# tester.net
KiCad netlist of a schematic drawn in EAGLE
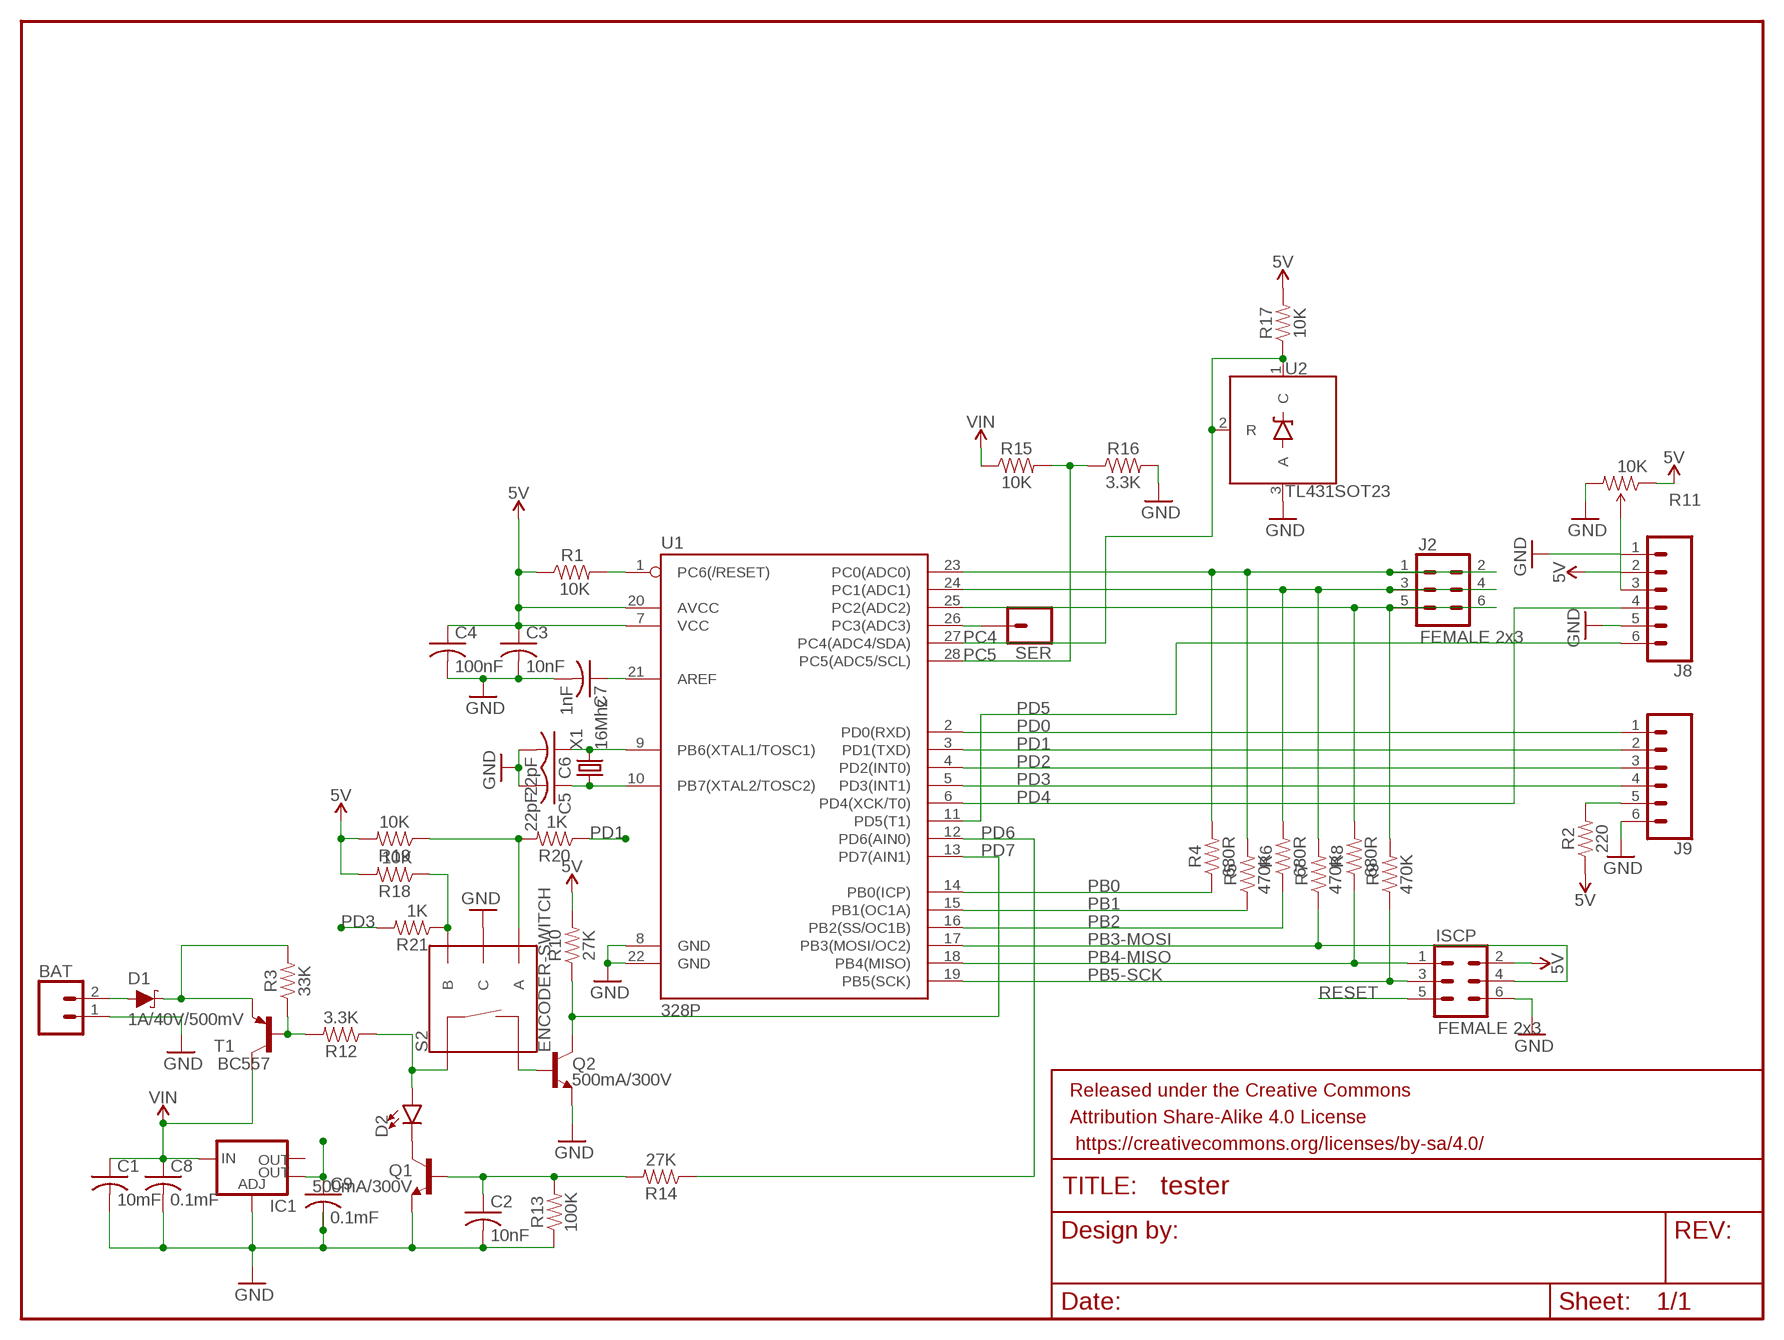
[diagram p0: schematic, sheet 1]

(export (version "E")
  (design (tool "Eeschema 10.0.6"))
  (components
    (comp (ref "BAT")
      (value "CONN_02")
      (footprint "eagle-import:1X02")
      (libsource (lib "eagle-import") (part "CONN_02"))
    )
    (comp (ref "C1")
      (value "10mF")
      (footprint "eagle-import:C0805")
      (libsource (lib "eagle-import") (part "C-USC0805"))
    )
    (comp (ref "C2")
      (value "10nF")
      (footprint "eagle-import:C0805")
      (libsource (lib "eagle-import") (part "C-USC0805"))
    )
    (comp (ref "C3")
      (value "10nF")
      (footprint "eagle-import:C0805")
      (libsource (lib "eagle-import") (part "C-USC0805"))
    )
    (comp (ref "C4")
      (value "100nF")
      (footprint "eagle-import:C0805")
      (libsource (lib "eagle-import") (part "C-USC0805"))
    )
    (comp (ref "C5")
      (value "22pF")
      (footprint "eagle-import:C0805")
      (libsource (lib "eagle-import") (part "C-USC0805"))
    )
    (comp (ref "C6")
      (value "22pF")
      (footprint "eagle-import:C0805")
      (libsource (lib "eagle-import") (part "C-USC0805"))
    )
    (comp (ref "C7")
      (value "1nF")
      (footprint "eagle-import:C0805")
      (libsource (lib "eagle-import") (part "C-USC0805"))
    )
    (comp (ref "C8")
      (value "0.1mF")
      (footprint "eagle-import:C0805")
      (libsource (lib "eagle-import") (part "C-USC0805"))
    )
    (comp (ref "C9")
      (value "0.1mF")
      (footprint "eagle-import:C0805")
      (libsource (lib "eagle-import") (part "C-USC0805"))
    )
    (comp (ref "D1")
      (value "1A/40V/500mV")
      (footprint "eagle-import:SMA-DIODE")
      (libsource (lib "eagle-import") (part "DIODE-SCHOTTKY-SS14"))
    )
    (comp (ref "D2")
      (value "LED3MM")
      (footprint "eagle-import:LED_3MM")
      (libsource (lib "eagle-import") (part "LED3MM"))
    )
    (comp (ref "FRAME1")
      (value "FRAME-LETTER")
      (footprint "eagle-import:CREATIVE_COMMONS")
      (libsource (lib "eagle-import") (part "FRAME-LETTER"))
    )
    (comp (ref "IC1")
      (value "V_REG_LM1117SOT223")
      (footprint "eagle-import:SOT223")
      (libsource (lib "eagle-import") (part "V_REG_LM1117SOT223"))
    )
    (comp (ref "ISCP")
      (value "FEMALE 2x3")
      (footprint "eagle-import:2X3")
      (libsource (lib "eagle-import") (part "CONN_03X2FEMALE"))
    )
    (comp (ref "J2")
      (value "FEMALE 2x3")
      (footprint "eagle-import:2X3")
      (libsource (lib "eagle-import") (part "CONN_03X2FEMALE"))
    )
    (comp (ref "J8")
      (value "CONN_06SILK_FEMALE_PTH")
      (footprint "eagle-import:1X06")
      (libsource (lib "eagle-import") (part "CONN_06SILK_FEMALE_PTH"))
    )
    (comp (ref "J9")
      (value "CONN_06SILK_FEMALE_PTH")
      (footprint "eagle-import:1X06")
      (libsource (lib "eagle-import") (part "CONN_06SILK_FEMALE_PTH"))
    )
    (comp (ref "Q1")
      (value "500mA/300V")
      (footprint "eagle-import:SOT23-3")
      (libsource (lib "eagle-import") (part "TRANS_NPN-MMBTA42"))
    )
    (comp (ref "Q2")
      (value "500mA/300V")
      (footprint "eagle-import:SOT23-3")
      (libsource (lib "eagle-import") (part "TRANS_NPN-MMBTA42"))
    )
    (comp (ref "R1")
      (value "10K")
      (footprint "eagle-import:0805")
      (libsource (lib "eagle-import") (part "RESISTOR0805"))
    )
    (comp (ref "R2")
      (value "220")
      (footprint "eagle-import:1206")
      (libsource (lib "eagle-import") (part "RESISTOR1206"))
    )
    (comp (ref "R3")
      (value "33K")
      (footprint "eagle-import:1206")
      (libsource (lib "eagle-import") (part "RESISTOR1206"))
    )
    (comp (ref "R4")
      (value "680R")
      (footprint "eagle-import:AXIAL-0.3")
      (libsource (lib "eagle-import") (part "RESISTORAXIAL-0.3"))
    )
    (comp (ref "R5")
      (value "470K")
      (footprint "eagle-import:AXIAL-0.3")
      (libsource (lib "eagle-import") (part "RESISTORAXIAL-0.3"))
    )
    (comp (ref "R6")
      (value "680R")
      (footprint "eagle-import:AXIAL-0.3")
      (libsource (lib "eagle-import") (part "RESISTORAXIAL-0.3"))
    )
    (comp (ref "R7")
      (value "470K")
      (footprint "eagle-import:AXIAL-0.3")
      (libsource (lib "eagle-import") (part "RESISTORAXIAL-0.3"))
    )
    (comp (ref "R8")
      (value "680R")
      (footprint "eagle-import:AXIAL-0.3")
      (libsource (lib "eagle-import") (part "RESISTORAXIAL-0.3"))
    )
    (comp (ref "R9")
      (value "470K")
      (footprint "eagle-import:AXIAL-0.3")
      (libsource (lib "eagle-import") (part "RESISTORAXIAL-0.3"))
    )
    (comp (ref "R10")
      (value "27K")
      (footprint "eagle-import:1206")
      (libsource (lib "eagle-import") (part "RESISTOR1206"))
    )
    (comp (ref "R11")
      (value "10K")
      (footprint "eagle-import:TRIM_POT_PTH")
      (libsource (lib "eagle-import") (part "TRIMPOTPTH"))
    )
    (comp (ref "R12")
      (value "3.3K")
      (footprint "eagle-import:1206")
      (libsource (lib "eagle-import") (part "RESISTOR1206"))
    )
    (comp (ref "R13")
      (value "100K")
      (footprint "eagle-import:0805")
      (libsource (lib "eagle-import") (part "RESISTOR0805"))
    )
    (comp (ref "R14")
      (value "27K")
      (footprint "eagle-import:1206")
      (libsource (lib "eagle-import") (part "RESISTOR1206"))
    )
    (comp (ref "R15")
      (value "10K")
      (footprint "eagle-import:1206")
      (libsource (lib "eagle-import") (part "RESISTOR1206"))
    )
    (comp (ref "R16")
      (value "3.3K")
      (footprint "eagle-import:1206")
      (libsource (lib "eagle-import") (part "RESISTOR1206"))
    )
    (comp (ref "R17")
      (value "10K")
      (footprint "eagle-import:0805")
      (libsource (lib "eagle-import") (part "RESISTOR0805"))
    )
    (comp (ref "R18")
      (value "10K")
      (footprint "eagle-import:0805")
      (libsource (lib "eagle-import") (part "RESISTOR0805"))
    )
    (comp (ref "R19")
      (value "10K")
      (footprint "eagle-import:0805")
      (libsource (lib "eagle-import") (part "RESISTOR0805"))
    )
    (comp (ref "R20")
      (value "1K")
      (footprint "eagle-import:0805")
      (libsource (lib "eagle-import") (part "RESISTOR0805"))
    )
    (comp (ref "R21")
      (value "1K")
      (footprint "eagle-import:0805")
      (libsource (lib "eagle-import") (part "RESISTOR0805"))
    )
    (comp (ref "S2")
      (value "ENCODER-SWITCH")
      (footprint "eagle-import:ROTARY_ENC_PLAIN")
      (libsource (lib "eagle-import") (part "ENCODER-SWITCH"))
    )
    (comp (ref "SER")
      (value "CONN_01")
      (footprint "eagle-import:1X01")
      (libsource (lib "eagle-import") (part "CONN_01"))
    )
    (comp (ref "T1")
      (value "BC557")
      (footprint "eagle-import:TO92-EBC")
      (libsource (lib "eagle-import") (part "-PNP-TO92-EBCBC557A"))
    )
    (comp (ref "U1")
      (value "328P")
      (footprint "eagle-import:DIP28")
      (libsource (lib "eagle-import") (part "ATMEGA328P_PDIP"))
    )
    (comp (ref "U2")
      (value "TL431SOT23")
      (footprint "eagle-import:SOT23-3")
      (libsource (lib "eagle-import") (part "TL431SOT23"))
    )
    (comp (ref "X1")
      (value "16Mhz")
      (footprint "eagle-import:HC49")
      (libsource (lib "eagle-import") (part "CRYSTALS-NOGND-HC49"))
    )
  )
  (nets
    (net (code "1") (name "/PB0") (class "Default")
      (node (ref "R4") (pin "P$1") (pinfunction "1_P$1") (pintype "passive"))
      (node (ref "U1") (pin "14") (pinfunction "PB0(ICP)_14") (pintype "bidirectional"))
    )
    (net (code "2") (name "/PB1") (class "Default")
      (node (ref "R5") (pin "P$1") (pinfunction "1_P$1") (pintype "passive"))
      (node (ref "U1") (pin "15") (pinfunction "PB1(OC1A)_15") (pintype "bidirectional"))
    )
    (net (code "3") (name "/PB2") (class "Default")
      (node (ref "R6") (pin "P$1") (pinfunction "1_P$1") (pintype "passive"))
      (node (ref "U1") (pin "16") (pinfunction "PB2(SS/OC1B)_16") (pintype "bidirectional"))
    )
    (net (code "4") (name "/PB3-MOSI") (class "Default")
      (node (ref "ISCP") (pin "4") (pinfunction "4_4") (pintype "bidirectional"))
      (node (ref "R7") (pin "P$1") (pinfunction "1_P$1") (pintype "passive"))
      (node (ref "U1") (pin "17") (pinfunction "PB3(MOSI/OC2)_17") (pintype "bidirectional"))
    )
    (net (code "5") (name "/PB4-MISO") (class "Default")
      (node (ref "ISCP") (pin "1") (pinfunction "1_1") (pintype "bidirectional"))
      (node (ref "R8") (pin "P$1") (pinfunction "1_P$1") (pintype "passive"))
      (node (ref "U1") (pin "18") (pinfunction "PB4(MISO)_18") (pintype "bidirectional"))
    )
    (net (code "6") (name "/PB5-SCK") (class "Default")
      (node (ref "ISCP") (pin "3") (pinfunction "3_3") (pintype "bidirectional"))
      (node (ref "R9") (pin "P$1") (pinfunction "1_P$1") (pintype "passive"))
      (node (ref "U1") (pin "19") (pinfunction "PB5(SCK)_19") (pintype "bidirectional"))
    )
    (net (code "7") (name "/PC4") (class "Default")
      (node (ref "R17") (pin "1") (pinfunction "1_1") (pintype "passive"))
      (node (ref "U1") (pin "27") (pinfunction "PC4(ADC4/SDA)_27") (pintype "bidirectional"))
      (node (ref "U2") (pin "1") (pinfunction "C_1") (pintype "bidirectional"))
      (node (ref "U2") (pin "2") (pinfunction "R_2") (pintype "bidirectional"))
    )
    (net (code "8") (name "/PC5") (class "Default")
      (node (ref "R15") (pin "2") (pinfunction "2_2") (pintype "passive"))
      (node (ref "R16") (pin "1") (pinfunction "1_1") (pintype "passive"))
      (node (ref "U1") (pin "28") (pinfunction "PC5(ADC5/SCL)_28") (pintype "bidirectional"))
    )
    (net (code "9") (name "/PD0") (class "Default")
      (node (ref "J9") (pin "1") (pinfunction "1_1") (pintype "passive"))
      (node (ref "U1") (pin "2") (pinfunction "PD0(RXD)_2") (pintype "bidirectional"))
    )
    (net (code "10") (name "/PD1") (class "Default")
      (node (ref "J9") (pin "2") (pinfunction "2_2") (pintype "passive"))
      (node (ref "R20") (pin "1") (pinfunction "1_1") (pintype "passive"))
      (node (ref "U1") (pin "3") (pinfunction "PD1(TXD)_3") (pintype "bidirectional"))
    )
    (net (code "11") (name "/PD2") (class "Default")
      (node (ref "J9") (pin "3") (pinfunction "3_3") (pintype "passive"))
      (node (ref "U1") (pin "4") (pinfunction "PD2(INT0)_4") (pintype "bidirectional"))
    )
    (net (code "12") (name "/PD3") (class "Default")
      (node (ref "J9") (pin "4") (pinfunction "4_4") (pintype "passive"))
      (node (ref "R21") (pin "2") (pinfunction "2_2") (pintype "passive"))
      (node (ref "U1") (pin "5") (pinfunction "PD3(INT1)_5") (pintype "bidirectional"))
    )
    (net (code "13") (name "/PD4") (class "Default")
      (node (ref "J8") (pin "4") (pinfunction "4_4") (pintype "passive"))
      (node (ref "U1") (pin "6") (pinfunction "PD4(XCK/T0)_6") (pintype "bidirectional"))
    )
    (net (code "14") (name "/PD5") (class "Default")
      (node (ref "J8") (pin "6") (pinfunction "6_6") (pintype "passive"))
      (node (ref "U1") (pin "11") (pinfunction "PD5(T1)_11") (pintype "bidirectional"))
    )
    (net (code "15") (name "/PD6") (class "Default")
      (node (ref "R14") (pin "1") (pinfunction "1_1") (pintype "passive"))
      (node (ref "U1") (pin "12") (pinfunction "PD6(AIN0)_12") (pintype "bidirectional"))
    )
    (net (code "16") (name "/PD7") (class "Default")
      (node (ref "Q2") (pin "3") (pinfunction "C_3") (pintype "passive"))
      (node (ref "R10") (pin "1") (pinfunction "1_1") (pintype "passive"))
      (node (ref "U1") (pin "13") (pinfunction "PD7(AIN1)_13") (pintype "bidirectional"))
    )
    (net (code "17") (name "/RESET") (class "Default")
      (node (ref "ISCP") (pin "5") (pinfunction "5_5") (pintype "bidirectional"))
      (node (ref "R1") (pin "2") (pinfunction "2_2") (pintype "passive"))
      (node (ref "U1") (pin "1") (pinfunction "PC6(/RESET)_1") (pintype "bidirectional"))
    )
    (net (code "18") (name "5V") (class "Default")
      (node (ref "C3") (pin "1") (pinfunction "1_1") (pintype "passive"))
      (node (ref "C4") (pin "1") (pinfunction "1_1") (pintype "passive"))
      (node (ref "C9") (pin "1") (pinfunction "1_1") (pintype "passive"))
      (node (ref "IC1") (pin "4") (pinfunction "OUT_4") (pintype "output"))
      (node (ref "ISCP") (pin "2") (pinfunction "2_2") (pintype "bidirectional"))
      (node (ref "J8") (pin "2") (pinfunction "2_2") (pintype "passive"))
      (node (ref "R1") (pin "1") (pinfunction "1_1") (pintype "passive"))
      (node (ref "R10") (pin "2") (pinfunction "2_2") (pintype "passive"))
      (node (ref "R11") (pin "1") (pinfunction "CCW_1") (pintype "passive"))
      (node (ref "R17") (pin "2") (pinfunction "2_2") (pintype "passive"))
      (node (ref "R18") (pin "2") (pinfunction "2_2") (pintype "passive"))
      (node (ref "R19") (pin "2") (pinfunction "2_2") (pintype "passive"))
      (node (ref "R2") (pin "1") (pinfunction "1_1") (pintype "passive"))
      (node (ref "U1") (pin "20") (pinfunction "AVCC_20") (pintype "bidirectional"))
      (node (ref "U1") (pin "7") (pinfunction "VCC_7") (pintype "bidirectional"))
    )
    (net (code "19") (name "GND") (class "Default")
      (node (ref "BAT") (pin "1") (pinfunction "1_1") (pintype "passive"))
      (node (ref "C1") (pin "2") (pinfunction "2_2") (pintype "passive"))
      (node (ref "C2") (pin "2") (pinfunction "2_2") (pintype "passive"))
      (node (ref "C3") (pin "2") (pinfunction "2_2") (pintype "passive"))
      (node (ref "C4") (pin "2") (pinfunction "2_2") (pintype "passive"))
      (node (ref "C5") (pin "2") (pinfunction "2_2") (pintype "passive"))
      (node (ref "C6") (pin "2") (pinfunction "2_2") (pintype "passive"))
      (node (ref "C7") (pin "2") (pinfunction "2_2") (pintype "passive"))
      (node (ref "C8") (pin "2") (pinfunction "2_2") (pintype "passive"))
      (node (ref "C9") (pin "2") (pinfunction "2_2") (pintype "passive"))
      (node (ref "IC1") (pin "1") (pinfunction "ADJ_1") (pintype "input"))
      (node (ref "ISCP") (pin "6") (pinfunction "6_6") (pintype "bidirectional"))
      (node (ref "J8") (pin "1") (pinfunction "1_1") (pintype "passive"))
      (node (ref "J8") (pin "5") (pinfunction "5_5") (pintype "passive"))
      (node (ref "J9") (pin "6") (pinfunction "6_6") (pintype "passive"))
      (node (ref "Q1") (pin "2") (pinfunction "E_2") (pintype "passive"))
      (node (ref "Q2") (pin "2") (pinfunction "E_2") (pintype "passive"))
      (node (ref "R11") (pin "3") (pinfunction "CW_3") (pintype "passive"))
      (node (ref "R13") (pin "1") (pinfunction "1_1") (pintype "passive"))
      (node (ref "R16") (pin "2") (pinfunction "2_2") (pintype "passive"))
      (node (ref "S2") (pin "C") (pinfunction "C_C") (pintype "bidirectional"))
      (node (ref "U1") (pin "22") (pinfunction "GND_22") (pintype "bidirectional"))
      (node (ref "U1") (pin "8") (pinfunction "GND_8") (pintype "bidirectional"))
      (node (ref "U2") (pin "3") (pinfunction "A_3") (pintype "bidirectional"))
    )
    (net (code "20") (name "Net-(BAT-Pad2)") (class "Default")
      (node (ref "BAT") (pin "2") (pinfunction "2_2") (pintype "passive"))
      (node (ref "D1") (pin "A") (pinfunction "A_A") (pintype "passive"))
    )
    (net (code "21") (name "Net-(D1-PadC)") (class "Default")
      (node (ref "D1") (pin "C") (pinfunction "C_C") (pintype "passive"))
      (node (ref "R3") (pin "2") (pinfunction "2_2") (pintype "passive"))
      (node (ref "T1") (pin "E") (pinfunction "E_E") (pintype "passive"))
    )
    (net (code "22") (name "Net-(D2-C)") (class "Default")
      (node (ref "D2") (pin "K") (pinfunction "C_K") (pintype "passive"))
      (node (ref "Q1") (pin "3") (pinfunction "C_3") (pintype "passive"))
    )
    (net (code "23") (name "Net-(D2-PadA)") (class "Default")
      (node (ref "D2") (pin "A") (pinfunction "A_A") (pintype "passive"))
      (node (ref "R12") (pin "1") (pinfunction "1_1") (pintype "passive"))
      (node (ref "S2") (pin "SW+") (pinfunction "SW+_SW+") (pintype "bidirectional"))
    )
    (net (code "24") (name "Net-(J9-Pad5)") (class "Default")
      (node (ref "J9") (pin "5") (pinfunction "5_5") (pintype "passive"))
      (node (ref "R2") (pin "2") (pinfunction "2_2") (pintype "passive"))
    )
    (net (code "25") (name "Net-(Q1-B)") (class "Default")
      (node (ref "C2") (pin "1") (pinfunction "1_1") (pintype "passive"))
      (node (ref "Q1") (pin "1") (pinfunction "B_1") (pintype "passive"))
      (node (ref "R13") (pin "2") (pinfunction "2_2") (pintype "passive"))
      (node (ref "R14") (pin "2") (pinfunction "2_2") (pintype "passive"))
    )
    (net (code "26") (name "Net-(Q2-B)") (class "Default")
      (node (ref "Q2") (pin "1") (pinfunction "B_1") (pintype "passive"))
      (node (ref "S2") (pin "SW-") (pinfunction "SW-_SW-") (pintype "bidirectional"))
    )
    (net (code "27") (name "Net-(R4-2)") (class "Default")
      (node (ref "J2") (pin "1") (pinfunction "1_1") (pintype "bidirectional"))
      (node (ref "J2") (pin "2") (pinfunction "2_2") (pintype "bidirectional"))
      (node (ref "R4") (pin "P$2") (pinfunction "2_P$2") (pintype "passive"))
      (node (ref "R5") (pin "P$2") (pinfunction "2_P$2") (pintype "passive"))
      (node (ref "U1") (pin "23") (pinfunction "PC0(ADC0)_23") (pintype "bidirectional"))
    )
    (net (code "28") (name "Net-(R6-2)") (class "Default")
      (node (ref "J2") (pin "3") (pinfunction "3_3") (pintype "bidirectional"))
      (node (ref "J2") (pin "4") (pinfunction "4_4") (pintype "bidirectional"))
      (node (ref "R6") (pin "P$2") (pinfunction "2_P$2") (pintype "passive"))
      (node (ref "R7") (pin "P$2") (pinfunction "2_P$2") (pintype "passive"))
      (node (ref "U1") (pin "24") (pinfunction "PC1(ADC1)_24") (pintype "bidirectional"))
    )
    (net (code "29") (name "Net-(R8-2)") (class "Default")
      (node (ref "J2") (pin "5") (pinfunction "5_5") (pintype "bidirectional"))
      (node (ref "J2") (pin "6") (pinfunction "6_6") (pintype "bidirectional"))
      (node (ref "R8") (pin "P$2") (pinfunction "2_P$2") (pintype "passive"))
      (node (ref "R9") (pin "P$2") (pinfunction "2_P$2") (pintype "passive"))
      (node (ref "U1") (pin "25") (pinfunction "PC2(ADC2)_25") (pintype "bidirectional"))
    )
    (net (code "30") (name "Net-(R11-WIPER)") (class "Default")
      (node (ref "J8") (pin "3") (pinfunction "3_3") (pintype "passive"))
      (node (ref "R11") (pin "2") (pinfunction "WIPER_2") (pintype "passive"))
    )
    (net (code "31") (name "Net-(R12-Pad2)") (class "Default")
      (node (ref "R12") (pin "2") (pinfunction "2_2") (pintype "passive"))
      (node (ref "R3") (pin "1") (pinfunction "1_1") (pintype "passive"))
      (node (ref "T1") (pin "B") (pinfunction "B_B") (pintype "passive"))
    )
    (net (code "32") (name "Net-(R18-Pad1)") (class "Default")
      (node (ref "R18") (pin "1") (pinfunction "1_1") (pintype "passive"))
      (node (ref "R21") (pin "1") (pinfunction "1_1") (pintype "passive"))
      (node (ref "S2") (pin "B") (pinfunction "B_B") (pintype "bidirectional"))
    )
    (net (code "33") (name "Net-(R19-Pad1)") (class "Default")
      (node (ref "R19") (pin "1") (pinfunction "1_1") (pintype "passive"))
      (node (ref "R20") (pin "2") (pinfunction "2_2") (pintype "passive"))
      (node (ref "S2") (pin "A") (pinfunction "A_A") (pintype "bidirectional"))
    )
    (net (code "34") (name "Net-(U1-AREF)") (class "Default")
      (node (ref "C7") (pin "1") (pinfunction "1_1") (pintype "passive"))
      (node (ref "U1") (pin "21") (pinfunction "AREF_21") (pintype "bidirectional"))
    )
    (net (code "35") (name "Net-(U1-PB6(XTAL1{slash}TOSC1))") (class "Default")
      (node (ref "C6") (pin "1") (pinfunction "1_1") (pintype "passive"))
      (node (ref "U1") (pin "9") (pinfunction "PB6(XTAL1/TOSC1)_9") (pintype "bidirectional"))
      (node (ref "X1") (pin "2") (pinfunction "2_2") (pintype "passive"))
    )
    (net (code "36") (name "Net-(U1-PB7(XTAL2{slash}TOSC2))") (class "Default")
      (node (ref "C5") (pin "1") (pinfunction "1_1") (pintype "passive"))
      (node (ref "U1") (pin "10") (pinfunction "PB7(XTAL2/TOSC2)_10") (pintype "bidirectional"))
      (node (ref "X1") (pin "1") (pinfunction "1_1") (pintype "passive"))
    )
    (net (code "37") (name "Net-(U1-PC3(ADC3))") (class "Default")
      (node (ref "SER") (pin "1") (pinfunction "1_1") (pintype "passive"))
      (node (ref "U1") (pin "26") (pinfunction "PC3(ADC3)_26") (pintype "bidirectional"))
    )
    (net (code "38") (name "VIN") (class "Default")
      (node (ref "C1") (pin "1") (pinfunction "1_1") (pintype "passive"))
      (node (ref "C8") (pin "1") (pinfunction "1_1") (pintype "passive"))
      (node (ref "IC1") (pin "3") (pinfunction "IN_3") (pintype "input"))
      (node (ref "R15") (pin "1") (pinfunction "1_1") (pintype "passive"))
      (node (ref "T1") (pin "C") (pinfunction "C_C") (pintype "passive"))
    )
    (net (code "39") (name "unconnected-(IC1-OUT-Pad2)") (class "Default")
      (node (ref "IC1") (pin "2") (pinfunction "OUT_2") (pintype "output"))
    )
  )
)
